# Main.net
KiCad netlist of a schematic drawn in Altium Designer
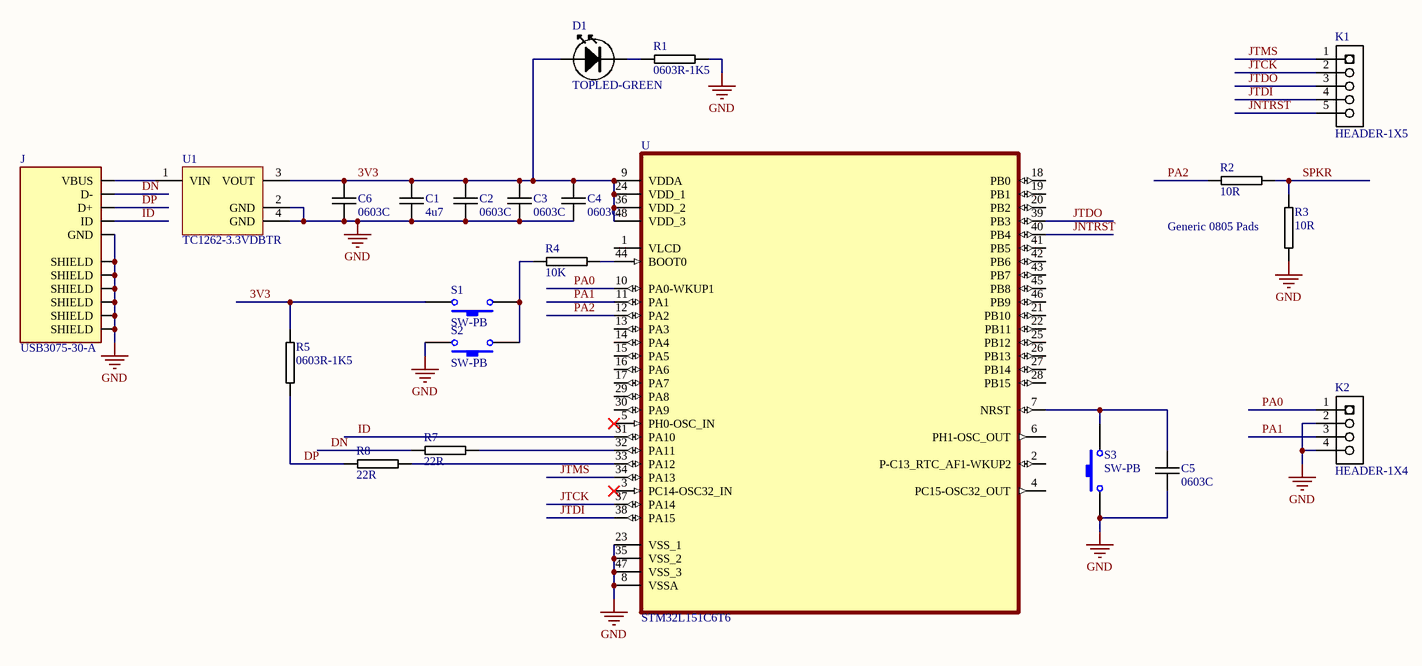
[diagram p0: Main.SchDoc]

(export (version "E")
  (design (tool "Eeschema 10.0.6"))
  (components
    (comp (ref "C1")
      (value "4u7")
      (footprint "1210C-GENERIC")
      (description "CAP CER 4.7UF 16V X7R 1210")
      (fields (field (name "MANUFACTURER") "Taiyo Yuden"))
      (libsource (lib "vh_altium_library") (part "1210C-4U7-16V-X7R-TAY"))
    )
    (comp (ref "C2")
      (value "0603C")
      (footprint "0603C-GENERIC")
      (description "CAPACITOR 0603 CERAMIC GENERIC")
      (libsource (lib "vh_altium_library") (part "0603C-GENERIC"))
    )
    (comp (ref "C3")
      (value "0603C")
      (footprint "0603C-GENERIC")
      (description "CAPACITOR 0603 CERAMIC GENERIC")
      (libsource (lib "vh_altium_library") (part "0603C-GENERIC"))
    )
    (comp (ref "C4")
      (value "0603C")
      (footprint "0603C-GENERIC")
      (description "CAPACITOR 0603 CERAMIC GENERIC")
      (libsource (lib "vh_altium_library") (part "0603C-GENERIC"))
    )
    (comp (ref "C5")
      (value "0603C")
      (footprint "0603C-GENERIC")
      (description "CAPACITOR 0603 CERAMIC GENERIC")
      (libsource (lib "vh_altium_library") (part "0603C-GENERIC"))
    )
    (comp (ref "C6")
      (value "0603C")
      (footprint "0603C-GENERIC")
      (description "CAPACITOR 0603 CERAMIC GENERIC")
      (libsource (lib "vh_altium_library") (part "0603C-GENERIC"))
    )
    (comp (ref "D1")
      (value "TOPLED-GREEN")
      (footprint "TOPLED-GREEN")
      (libsource (lib "vh_altium_library") (part "TOPLED-GREEN"))
    )
    (comp (ref "J")
      (value "USB3075-30-A")
      (footprint "GCT_USB3075-30-A")
      (description "USB - micro B USB 2.0 Receptacle Connector 5 Position Surface Mount, Right Angle; Through Hole")
      (fields
        (field (name "MF") "Global Connector Technology")
        (field (name "DIGI-KEY_PART_NUMBER") "2073-USB3075-30-ACT-ND")
      )
      (libsource (lib "USB3075-30-A") (part "USB3075-30-A"))
    )
    (comp (ref "K1")
      (value "HEADER-1X5")
      (footprint "HEADER-1X5")
      (description "PINHEADER 1X5")
      (libsource (lib "vh_altium_library") (part "HEADER-1X5"))
    )
    (comp (ref "K2")
      (value "HEADER-1X4")
      (footprint "HEADER-1X4")
      (libsource (lib "vh_altium_library") (part "HEADER-1X4"))
    )
    (comp (ref "R1")
      (value "0603R-1K5")
      (footprint "0603R-1k5")
      (description "GENERIC RESISTOR 0603")
      (fields (field (name "MANUFACTURER PART NUMBER") "RMCF 1/16 15K 1% R") (field (name "TOLERANCE") "±1%"))
      (libsource (lib "vh_altium_library") (part "0603R-1K5"))
    )
    (comp (ref "R2")
      (value "10R")
      (footprint "0805R-10")
      (description "RESISTOR 0805 1/4 WATT THIN FILM")
      (libsource (lib "vh_altium_library") (part "0805R-10"))
    )
    (comp (ref "R3")
      (value "10R")
      (footprint "0805R-10")
      (description "RESISTOR 0805 1/4 WATT THIN FILM")
      (libsource (lib "vh_altium_library") (part "0805R-10"))
    )
    (comp (ref "R4")
      (value "10K")
      (footprint "0603R-10K")
      (description "GENERIC RESISTOR 0603")
      (fields (field (name "MANUFACTURER") "Stackpole Electronics Inc") (field (name "TOLERANCE") "±1%"))
      (libsource (lib "vh_altium_library") (part "0603R-10K"))
    )
    (comp (ref "R5")
      (value "0603R-1K5")
      (footprint "0603R-1k5")
      (description "GENERIC RESISTOR 0603")
      (fields (field (name "MANUFACTURER PART NUMBER") "RMCF 1/16 15K 1% R") (field (name "TOLERANCE") "±1%"))
      (libsource (lib "vh_altium_library") (part "0603R-1K5"))
    )
    (comp (ref "R7")
      (value "22R")
      (footprint "0603R-22")
      (description "RES TF 1/10W 22 OHM 1% 0603")
      (fields (field (name "TOLERANCE") "±1%"))
      (libsource (lib "vh_altium_library") (part "0603R-22R"))
    )
    (comp (ref "R8")
      (value "22R")
      (footprint "0603R-22")
      (description "RES TF 1/10W 22 OHM 1% 0603")
      (fields (field (name "TOLERANCE") "±1%"))
      (libsource (lib "vh_altium_library") (part "0603R-22R"))
    )
    (comp (ref "S1")
      (value "SW-PB")
      (footprint "SPST-2")
      (description "Switch")
      (fields (field (name "PUBLISHER") "Altium Limited"))
      (libsource (lib "Miscellaneous Devices") (part "SW-PB"))
    )
    (comp (ref "S2")
      (value "SW-PB")
      (footprint "SPST-2")
      (description "Switch")
      (fields (field (name "PUBLISHER") "Altium Limited"))
      (libsource (lib "Miscellaneous Devices") (part "SW-PB"))
    )
    (comp (ref "S3")
      (value "SW-PB")
      (footprint "SPST-2")
      (description "Switch")
      (fields (field (name "PUBLISHER") "Altium Limited"))
      (libsource (lib "Miscellaneous Devices") (part "SW-PB"))
    )
    (comp (ref "U")
      (value "STM32L151C6T6")
      (footprint "QFP50P900X900X160-48N")
      (description "ARM® Cortex®-M3 STM32L1 Microcontroller IC 32-Bit 32MHz 32KB _32K x 8_ FLASH 48-LQFP _7x7_")
      (fields (field (name "MF") "STMicroelectronics"))
      (libsource (lib "STM32L151C6T6") (part "STM32L151C6T6"))
    )
    (comp (ref "U1")
      (value "TC1262-3.3VDBTR")
      (footprint "SOT-223-DB3_N")
      (description "500mA Fixed Output CMOS LDO, 3-Pin SOT-223, Extended Temperature, Tape and Reel")
      (fields (field (name "PUBLISHER") "Altium Limited"))
      (libsource (lib "Microchip Power Mgt Line Regulator") (part "TC1262-3.3VDBTR"))
    )
  )
  (nets
    (net (code "1") (name "/3V3") (class "Default")
      (node (ref "C1") (pin "1") (pintype "passive"))
      (node (ref "C2") (pin "1") (pintype "passive"))
      (node (ref "C3") (pin "1") (pintype "passive"))
      (node (ref "C4") (pin "1") (pintype "passive"))
      (node (ref "C6") (pin "1") (pintype "passive"))
      (node (ref "D1") (pin "A") (pintype "passive"))
      (node (ref "R5") (pin "1") (pintype "passive"))
      (node (ref "S1") (pin "2") (pinfunction "2_2") (pintype "passive"))
      (node (ref "U") (pin "24") (pinfunction "VDD_1_24") (pintype "power_in"))
      (node (ref "U") (pin "36") (pinfunction "VDD_2_36") (pintype "power_in"))
      (node (ref "U") (pin "48") (pinfunction "VDD_3_48") (pintype "power_in"))
      (node (ref "U") (pin "9") (pinfunction "VDDA_9") (pintype "power_in"))
      (node (ref "U1") (pin "3") (pinfunction "VOUT_3") (pintype "power_in"))
    )
    (net (code "2") (name "/DN") (class "Default")
      (node (ref "J") (pin "2") (pinfunction "D-_2") (pintype "bidirectional"))
      (node (ref "R7") (pin "1") (pintype "passive"))
    )
    (net (code "3") (name "/DP") (class "Default")
      (node (ref "J") (pin "3") (pinfunction "D+_3") (pintype "bidirectional"))
      (node (ref "R5") (pin "2") (pintype "passive"))
      (node (ref "R8") (pin "1") (pintype "passive"))
    )
    (net (code "4") (name "/ID") (class "Default")
      (node (ref "J") (pin "4") (pinfunction "ID_4") (pintype "bidirectional"))
      (node (ref "U") (pin "31") (pinfunction "PA10_31") (pintype "bidirectional"))
    )
    (net (code "5") (name "/JNTRST") (class "Default")
      (node (ref "K1") (pin "5") (pintype "passive"))
      (node (ref "U") (pin "40") (pinfunction "PB4_40") (pintype "bidirectional"))
    )
    (net (code "6") (name "/JTCK") (class "Default")
      (node (ref "K1") (pin "2") (pintype "passive"))
      (node (ref "U") (pin "37") (pinfunction "PA14_37") (pintype "bidirectional"))
    )
    (net (code "7") (name "/JTDI") (class "Default")
      (node (ref "K1") (pin "4") (pintype "passive"))
      (node (ref "U") (pin "38") (pinfunction "PA15_38") (pintype "bidirectional"))
    )
    (net (code "8") (name "/JTDO") (class "Default")
      (node (ref "K1") (pin "3") (pintype "passive"))
      (node (ref "U") (pin "39") (pinfunction "PB3_39") (pintype "bidirectional"))
    )
    (net (code "9") (name "/JTMS") (class "Default")
      (node (ref "K1") (pin "1") (pintype "passive"))
      (node (ref "U") (pin "34") (pinfunction "PA13_34") (pintype "bidirectional"))
    )
    (net (code "10") (name "/PA0") (class "Default")
      (node (ref "K2") (pin "1") (pintype "passive"))
      (node (ref "U") (pin "10") (pinfunction "PA0-WKUP1_10") (pintype "bidirectional"))
    )
    (net (code "11") (name "/PA1") (class "Default")
      (node (ref "K2") (pin "3") (pintype "passive"))
      (node (ref "U") (pin "11") (pinfunction "PA1_11") (pintype "bidirectional"))
    )
    (net (code "12") (name "/PA2") (class "Default")
      (node (ref "R2") (pin "1") (pintype "passive"))
      (node (ref "U") (pin "12") (pinfunction "PA2_12") (pintype "bidirectional"))
    )
    (net (code "13") (name "/SPKR") (class "Default")
      (node (ref "R2") (pin "2") (pintype "passive"))
      (node (ref "R3") (pin "2") (pintype "passive"))
    )
    (net (code "14") (name "GND") (class "Default")
      (node (ref "C1") (pin "2") (pintype "passive"))
      (node (ref "C2") (pin "2") (pintype "passive"))
      (node (ref "C3") (pin "2") (pintype "passive"))
      (node (ref "C4") (pin "2") (pintype "passive"))
      (node (ref "C5") (pin "2") (pintype "passive"))
      (node (ref "C6") (pin "2") (pintype "passive"))
      (node (ref "J") (pin "5") (pinfunction "GND_5") (pintype "power_in"))
      (node (ref "J") (pin "S1") (pinfunction "SHIELD_S1") (pintype "passive"))
      (node (ref "J") (pin "S2") (pinfunction "SHIELD_S2") (pintype "passive"))
      (node (ref "J") (pin "S3") (pinfunction "SHIELD_S3") (pintype "passive"))
      (node (ref "J") (pin "S4") (pinfunction "SHIELD_S4") (pintype "passive"))
      (node (ref "J") (pin "S5") (pinfunction "SHIELD_S5") (pintype "passive"))
      (node (ref "J") (pin "S6") (pinfunction "SHIELD_S6") (pintype "passive"))
      (node (ref "K2") (pin "2") (pintype "passive"))
      (node (ref "K2") (pin "4") (pintype "passive"))
      (node (ref "R1") (pin "2") (pintype "passive"))
      (node (ref "R3") (pin "1") (pintype "passive"))
      (node (ref "S2") (pin "2") (pinfunction "2_2") (pintype "passive"))
      (node (ref "S3") (pin "1") (pinfunction "1_1") (pintype "passive"))
      (node (ref "U") (pin "23") (pinfunction "VSS_1_23") (pintype "power_in"))
      (node (ref "U") (pin "35") (pinfunction "VSS_2_35") (pintype "power_in"))
      (node (ref "U") (pin "47") (pinfunction "VSS_3_47") (pintype "power_in"))
      (node (ref "U") (pin "8") (pinfunction "VSSA_8") (pintype "power_in"))
      (node (ref "U1") (pin "2") (pinfunction "GND_2") (pintype "power_in"))
      (node (ref "U1") (pin "4") (pinfunction "GND_4") (pintype "power_in"))
    )
    (net (code "15") (name "Net-(D1-PadK)") (class "Default")
      (node (ref "D1") (pin "K") (pintype "passive"))
      (node (ref "R1") (pin "1") (pintype "passive"))
    )
    (net (code "16") (name "Net-(J-VBUS)") (class "Default")
      (node (ref "J") (pin "1") (pinfunction "VBUS_1") (pintype "power_in"))
      (node (ref "U1") (pin "1") (pinfunction "VIN_1") (pintype "power_in"))
    )
    (net (code "17") (name "Net-(R4-Pad1)") (class "Default")
      (node (ref "R4") (pin "1") (pintype "passive"))
      (node (ref "S1") (pin "1") (pinfunction "1_1") (pintype "passive"))
      (node (ref "S2") (pin "1") (pinfunction "1_1") (pintype "passive"))
    )
    (net (code "18") (name "Net-(U-BOOT0)") (class "Default")
      (node (ref "R4") (pin "2") (pintype "passive"))
      (node (ref "U") (pin "44") (pinfunction "BOOT0_44") (pintype "input"))
    )
    (net (code "19") (name "Net-(U-NRST)") (class "Default")
      (node (ref "C5") (pin "1") (pintype "passive"))
      (node (ref "S3") (pin "2") (pinfunction "2_2") (pintype "passive"))
      (node (ref "U") (pin "7") (pinfunction "NRST_7") (pintype "bidirectional"))
    )
    (net (code "20") (name "Net-(U-PA11)") (class "Default")
      (node (ref "R7") (pin "2") (pintype "passive"))
      (node (ref "U") (pin "32") (pinfunction "PA11_32") (pintype "bidirectional"))
    )
    (net (code "21") (name "Net-(U-PA12)") (class "Default")
      (node (ref "R8") (pin "2") (pintype "passive"))
      (node (ref "U") (pin "33") (pinfunction "PA12_33") (pintype "bidirectional"))
    )
    (net (code "22") (name "unconnected-(U-P-C13_RTC_AF1-WKUP2-Pad2)") (class "Default")
      (node (ref "U") (pin "2") (pinfunction "P-C13_RTC_AF1-WKUP2_2") (pintype "bidirectional"))
    )
    (net (code "23") (name "unconnected-(U-PA3-Pad13)") (class "Default")
      (node (ref "U") (pin "13") (pinfunction "PA3_13") (pintype "bidirectional"))
    )
    (net (code "24") (name "unconnected-(U-PA4-Pad14)") (class "Default")
      (node (ref "U") (pin "14") (pinfunction "PA4_14") (pintype "bidirectional"))
    )
    (net (code "25") (name "unconnected-(U-PA5-Pad15)") (class "Default")
      (node (ref "U") (pin "15") (pinfunction "PA5_15") (pintype "bidirectional"))
    )
    (net (code "26") (name "unconnected-(U-PA6-Pad16)") (class "Default")
      (node (ref "U") (pin "16") (pinfunction "PA6_16") (pintype "bidirectional"))
    )
    (net (code "27") (name "unconnected-(U-PA7-Pad17)") (class "Default")
      (node (ref "U") (pin "17") (pinfunction "PA7_17") (pintype "bidirectional"))
    )
    (net (code "28") (name "unconnected-(U-PA8-Pad29)") (class "Default")
      (node (ref "U") (pin "29") (pinfunction "PA8_29") (pintype "bidirectional"))
    )
    (net (code "29") (name "unconnected-(U-PA9-Pad30)") (class "Default")
      (node (ref "U") (pin "30") (pinfunction "PA9_30") (pintype "bidirectional"))
    )
    (net (code "30") (name "unconnected-(U-PB0-Pad18)") (class "Default")
      (node (ref "U") (pin "18") (pinfunction "PB0_18") (pintype "bidirectional"))
    )
    (net (code "31") (name "unconnected-(U-PB1-Pad19)") (class "Default")
      (node (ref "U") (pin "19") (pinfunction "PB1_19") (pintype "bidirectional"))
    )
    (net (code "32") (name "unconnected-(U-PB2-Pad20)") (class "Default")
      (node (ref "U") (pin "20") (pinfunction "PB2_20") (pintype "bidirectional"))
    )
    (net (code "33") (name "unconnected-(U-PB5-Pad41)") (class "Default")
      (node (ref "U") (pin "41") (pinfunction "PB5_41") (pintype "bidirectional"))
    )
    (net (code "34") (name "unconnected-(U-PB6-Pad42)") (class "Default")
      (node (ref "U") (pin "42") (pinfunction "PB6_42") (pintype "bidirectional"))
    )
    (net (code "35") (name "unconnected-(U-PB7-Pad43)") (class "Default")
      (node (ref "U") (pin "43") (pinfunction "PB7_43") (pintype "bidirectional"))
    )
    (net (code "36") (name "unconnected-(U-PB8-Pad45)") (class "Default")
      (node (ref "U") (pin "45") (pinfunction "PB8_45") (pintype "bidirectional"))
    )
    (net (code "37") (name "unconnected-(U-PB9-Pad46)") (class "Default")
      (node (ref "U") (pin "46") (pinfunction "PB9_46") (pintype "bidirectional"))
    )
    (net (code "38") (name "unconnected-(U-PB10-Pad21)") (class "Default")
      (node (ref "U") (pin "21") (pinfunction "PB10_21") (pintype "bidirectional"))
    )
    (net (code "39") (name "unconnected-(U-PB11-Pad22)") (class "Default")
      (node (ref "U") (pin "22") (pinfunction "PB11_22") (pintype "bidirectional"))
    )
    (net (code "40") (name "unconnected-(U-PB12-Pad25)") (class "Default")
      (node (ref "U") (pin "25") (pinfunction "PB12_25") (pintype "bidirectional"))
    )
    (net (code "41") (name "unconnected-(U-PB13-Pad26)") (class "Default")
      (node (ref "U") (pin "26") (pinfunction "PB13_26") (pintype "bidirectional"))
    )
    (net (code "42") (name "unconnected-(U-PB14-Pad27)") (class "Default")
      (node (ref "U") (pin "27") (pinfunction "PB14_27") (pintype "bidirectional"))
    )
    (net (code "43") (name "unconnected-(U-PB15-Pad28)") (class "Default")
      (node (ref "U") (pin "28") (pinfunction "PB15_28") (pintype "bidirectional"))
    )
    (net (code "44") (name "unconnected-(U-PC14-OSC32_IN-Pad3)") (class "Default")
      (node (ref "U") (pin "3") (pinfunction "PC14-OSC32_IN_3") (pintype "input+no_connect"))
    )
    (net (code "45") (name "unconnected-(U-PC15-OSC32_OUT-Pad4)") (class "Default")
      (node (ref "U") (pin "4") (pinfunction "PC15-OSC32_OUT_4") (pintype "output"))
    )
    (net (code "46") (name "unconnected-(U-PH0-OSC_IN-Pad5)") (class "Default")
      (node (ref "U") (pin "5") (pinfunction "PH0-OSC_IN_5") (pintype "input+no_connect"))
    )
    (net (code "47") (name "unconnected-(U-PH1-OSC_OUT-Pad6)") (class "Default")
      (node (ref "U") (pin "6") (pinfunction "PH1-OSC_OUT_6") (pintype "output"))
    )
    (net (code "48") (name "unconnected-(U-VLCD-Pad1)") (class "Default")
      (node (ref "U") (pin "1") (pinfunction "VLCD_1") (pintype "power_in"))
    )
  )
)
